# Screen_v3.net
KiCad netlist of a schematic drawn in EAGLE
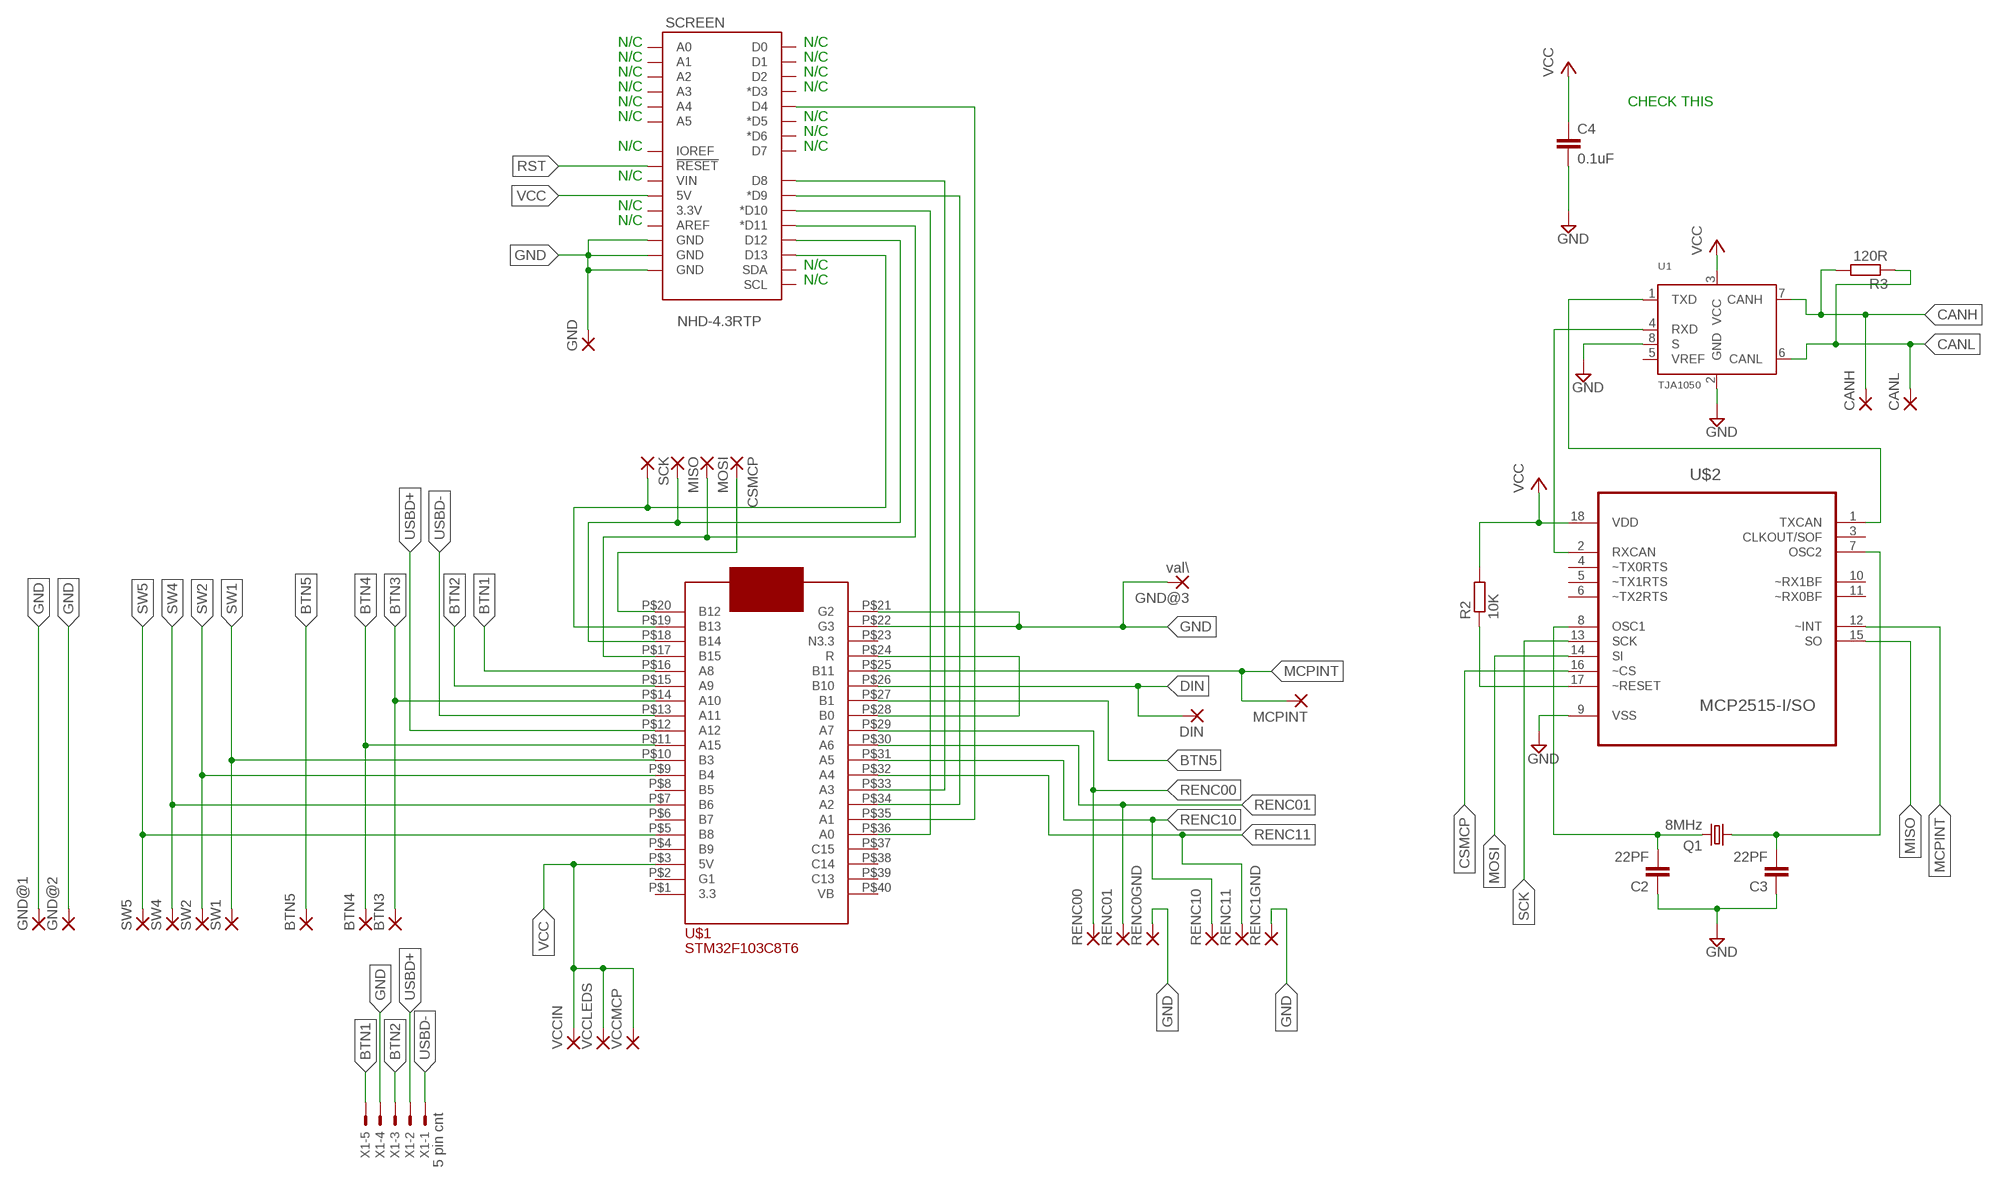
[diagram p0: schematic, sheet 1]

(export (version "E")
  (design (tool "Eeschema 10.0.6"))
  (components
    (comp (ref "BTN3")
      (value "SMD5")
      (footprint "eagle-import:SMD2,54-5,08")
      (libsource (lib "eagle-import") (part "SMD5"))
    )
    (comp (ref "BTN4")
      (value "SMD5")
      (footprint "eagle-import:SMD2,54-5,08")
      (libsource (lib "eagle-import") (part "SMD5"))
    )
    (comp (ref "BTN5")
      (value "SMD5")
      (footprint "eagle-import:SMD2,54-5,08")
      (libsource (lib "eagle-import") (part "SMD5"))
    )
    (comp (ref "C2")
      (value "22PF")
      (footprint "eagle-import:C0805")
      (libsource (lib "eagle-import") (part "C-EUC0805"))
    )
    (comp (ref "C3")
      (value "22PF")
      (footprint "eagle-import:C0805")
      (libsource (lib "eagle-import") (part "C-EUC0805"))
    )
    (comp (ref "C4")
      (value "0.1uF")
      (footprint "eagle-import:C0805")
      (libsource (lib "eagle-import") (part "C-EUC0805"))
    )
    (comp (ref "CANH")
      (value "SMD5")
      (footprint "eagle-import:SMD2,54-5,08")
      (libsource (lib "eagle-import") (part "SMD5"))
    )
    (comp (ref "CANL")
      (value "SMD5")
      (footprint "eagle-import:SMD2,54-5,08")
      (libsource (lib "eagle-import") (part "SMD5"))
    )
    (comp (ref "CSMCP")
      (value "SMD5")
      (footprint "eagle-import:SMD2,54-5,08")
      (libsource (lib "eagle-import") (part "SMD5"))
    )
    (comp (ref "DIN")
      (value "SMD5")
      (footprint "eagle-import:SMD2,54-5,08")
      (libsource (lib "eagle-import") (part "SMD5"))
    )
    (comp (ref "GND")
      (value "SMD5")
      (footprint "eagle-import:SMD2,54-5,08")
      (libsource (lib "eagle-import") (part "SMD5"))
    )
    (comp (ref "GND@1")
      (value "SMD5")
      (footprint "eagle-import:SMD2,54-5,08")
      (libsource (lib "eagle-import") (part "SMD5"))
    )
    (comp (ref "GND@2")
      (value "SMD5")
      (footprint "eagle-import:SMD2,54-5,08")
      (libsource (lib "eagle-import") (part "SMD5"))
    )
    (comp (ref "GND@3")
      (value "val\\")
      (footprint "eagle-import:SMD2,54-5,08")
      (libsource (lib "eagle-import") (part "SMD5"))
    )
    (comp (ref "MCPINT")
      (value "SMD5")
      (footprint "eagle-import:SMD2,54-5,08")
      (libsource (lib "eagle-import") (part "SMD5"))
    )
    (comp (ref "MISO")
      (value "SMD5")
      (footprint "eagle-import:SMD2,54-5,08")
      (libsource (lib "eagle-import") (part "SMD5"))
    )
    (comp (ref "MOSI")
      (value "SMD5")
      (footprint "eagle-import:SMD2,54-5,08")
      (libsource (lib "eagle-import") (part "SMD5"))
    )
    (comp (ref "Q1")
      (value "8MHz")
      (footprint "eagle-import:HC49_S")
      (libsource (lib "eagle-import") (part "CRYSTALHC49S"))
    )
    (comp (ref "R2")
      (value "10K")
      (footprint "eagle-import:M0805")
      (libsource (lib "eagle-import") (part "R-EU_M0805"))
    )
    (comp (ref "R3")
      (value "120R")
      (footprint "eagle-import:M0805")
      (libsource (lib "eagle-import") (part "R-EU_M0805"))
    )
    (comp (ref "RENC00")
      (value "SMD5")
      (footprint "eagle-import:SMD2,54-5,08")
      (libsource (lib "eagle-import") (part "SMD5"))
    )
    (comp (ref "RENC0GND")
      (value "SMD5")
      (footprint "eagle-import:SMD2,54-5,08")
      (libsource (lib "eagle-import") (part "SMD5"))
    )
    (comp (ref "RENC01")
      (value "SMD5")
      (footprint "eagle-import:SMD2,54-5,08")
      (libsource (lib "eagle-import") (part "SMD5"))
    )
    (comp (ref "RENC1GND")
      (value "SMD5")
      (footprint "eagle-import:SMD2,54-5,08")
      (libsource (lib "eagle-import") (part "SMD5"))
    )
    (comp (ref "RENC10")
      (value "SMD5")
      (footprint "eagle-import:SMD2,54-5,08")
      (libsource (lib "eagle-import") (part "SMD5"))
    )
    (comp (ref "RENC11")
      (value "SMD5")
      (footprint "eagle-import:SMD2,54-5,08")
      (libsource (lib "eagle-import") (part "SMD5"))
    )
    (comp (ref "SCK")
      (value "SMD5")
      (footprint "eagle-import:SMD2,54-5,08")
      (libsource (lib "eagle-import") (part "SMD5"))
    )
    (comp (ref "SCREEN")
      (value "NHD-4.3RTP")
      (footprint "eagle-import:NHD-4.3RTP")
      (libsource (lib "eagle-import") (part "NHD-4.3RTP"))
    )
    (comp (ref "SW1")
      (value "SMD5")
      (footprint "eagle-import:SMD2,54-5,08")
      (libsource (lib "eagle-import") (part "SMD5"))
    )
    (comp (ref "SW2")
      (value "SMD5")
      (footprint "eagle-import:SMD2,54-5,08")
      (libsource (lib "eagle-import") (part "SMD5"))
    )
    (comp (ref "SW4")
      (value "SMD5")
      (footprint "eagle-import:SMD2,54-5,08")
      (libsource (lib "eagle-import") (part "SMD5"))
    )
    (comp (ref "SW5")
      (value "SMD5")
      (footprint "eagle-import:SMD2,54-5,08")
      (libsource (lib "eagle-import") (part "SMD5"))
    )
    (comp (ref "U$1")
      (value "STM32F103C8T6DIP40")
      (footprint "eagle-import:STM32")
      (libsource (lib "eagle-import") (part "STM32F103C8T6DIP40"))
    )
    (comp (ref "U$2")
      (value "MCP2515-I/SO")
      (footprint "eagle-import:SOIC127P1034X264-18N")
      (fields (field (name "MF") "Microchip"))
      (libsource (lib "eagle-import") (part "MCP2515-I/SO"))
    )
    (comp (ref "U1")
      (value "TJA1050")
      (footprint "eagle-import:SOT96-1")
      (fields (field (name "MF") "NXP Semiconductors"))
      (libsource (lib "eagle-import") (part "TJA1050"))
    )
    (comp (ref "VCCIN")
      (value "SMD5")
      (footprint "eagle-import:SMD2,54-5,08")
      (libsource (lib "eagle-import") (part "SMD5"))
    )
    (comp (ref "VCCLEDS")
      (value "SMD5")
      (footprint "eagle-import:SMD2,54-5,08")
      (libsource (lib "eagle-import") (part "SMD5"))
    )
    (comp (ref "VCCMCP")
      (value "SMD5")
      (footprint "eagle-import:SMD2,54-5,08")
      (libsource (lib "eagle-import") (part "SMD5"))
    )
    (comp (ref "X1")
      (value "5 pin cnt")
      (footprint "eagle-import:JST-XH-05-PACKAGE-ROUND-PAD")
      (libsource (lib "eagle-import") (part "JST-XH-05-PIN-ROUND-PAD"))
    )
  )
  (nets
    (net (code "1") (name "BTN1") (class "Default")
      (node (ref "U$1") (pin "P$16") (pinfunction "A8_P$16") (pintype "bidirectional"))
      (node (ref "X1") (pin "5") (pinfunction "S_5") (pintype "passive"))
    )
    (net (code "2") (name "BTN2") (class "Default")
      (node (ref "U$1") (pin "P$15") (pinfunction "A9_P$15") (pintype "bidirectional"))
      (node (ref "X1") (pin "3") (pinfunction "S_3") (pintype "passive"))
    )
    (net (code "3") (name "BTN3") (class "Default")
      (node (ref "BTN3") (pin "1") (pinfunction "P_1") (pintype "passive"))
      (node (ref "U$1") (pin "P$14") (pinfunction "A10_P$14") (pintype "bidirectional"))
    )
    (net (code "4") (name "BTN4") (class "Default")
      (node (ref "BTN4") (pin "1") (pinfunction "P_1") (pintype "passive"))
      (node (ref "U$1") (pin "P$11") (pinfunction "A15_P$11") (pintype "bidirectional"))
    )
    (net (code "5") (name "BTN5") (class "Default")
      (node (ref "BTN5") (pin "1") (pinfunction "P_1") (pintype "passive"))
      (node (ref "U$1") (pin "P$27") (pinfunction "B1_P$27") (pintype "bidirectional"))
    )
    (net (code "6") (name "CANH") (class "Default")
      (node (ref "CANH") (pin "1") (pinfunction "P_1") (pintype "passive"))
      (node (ref "R3") (pin "2") (pinfunction "2_2") (pintype "passive"))
      (node (ref "U1") (pin "7") (pinfunction "CANH_7") (pintype "bidirectional"))
    )
    (net (code "7") (name "CANL") (class "Default")
      (node (ref "CANL") (pin "1") (pinfunction "P_1") (pintype "passive"))
      (node (ref "R3") (pin "1") (pinfunction "1_1") (pintype "passive"))
      (node (ref "U1") (pin "6") (pinfunction "CANL_6") (pintype "bidirectional"))
    )
    (net (code "8") (name "CSMCP") (class "Default")
      (node (ref "CSMCP") (pin "1") (pinfunction "P_1") (pintype "passive"))
      (node (ref "U$1") (pin "P$20") (pinfunction "B12_P$20") (pintype "bidirectional"))
      (node (ref "U$2") (pin "16") (pinfunction "~{CS}_16") (pintype "input"))
    )
    (net (code "9") (name "DIN") (class "Default")
      (node (ref "DIN") (pin "1") (pinfunction "P_1") (pintype "passive"))
      (node (ref "U$1") (pin "P$26") (pinfunction "B10_P$26") (pintype "bidirectional"))
    )
    (net (code "10") (name "GND") (class "Default")
      (node (ref "C2") (pin "1") (pinfunction "1_1") (pintype "passive"))
      (node (ref "C3") (pin "1") (pinfunction "1_1") (pintype "passive"))
      (node (ref "C4") (pin "2") (pinfunction "2_2") (pintype "passive"))
      (node (ref "GND") (pin "1") (pinfunction "P_1") (pintype "passive"))
      (node (ref "GND@1") (pin "1") (pinfunction "P_1") (pintype "passive"))
      (node (ref "GND@2") (pin "1") (pinfunction "P_1") (pintype "passive"))
      (node (ref "GND@3") (pin "1") (pinfunction "P_1") (pintype "passive"))
      (node (ref "RENC0GND") (pin "1") (pinfunction "P_1") (pintype "passive"))
      (node (ref "RENC1GND") (pin "1") (pinfunction "P_1") (pintype "passive"))
      (node (ref "SCREEN") (pin "GND@1") (pinfunction "GND_GND@1") (pintype "bidirectional"))
      (node (ref "SCREEN") (pin "GND@2") (pinfunction "GND_GND@2") (pintype "bidirectional"))
      (node (ref "SCREEN") (pin "GND@3") (pinfunction "GND_GND@3") (pintype "bidirectional"))
      (node (ref "U$1") (pin "P$21") (pinfunction "G2_P$21") (pintype "bidirectional"))
      (node (ref "U$1") (pin "P$22") (pinfunction "G3_P$22") (pintype "bidirectional"))
      (node (ref "U$2") (pin "9") (pinfunction "VSS_9") (pintype "power_in"))
      (node (ref "U1") (pin "2") (pinfunction "GND_2") (pintype "bidirectional"))
      (node (ref "U1") (pin "8") (pinfunction "S_8") (pintype "power_in"))
      (node (ref "X1") (pin "4") (pinfunction "S_4") (pintype "passive"))
    )
    (net (code "11") (name "MCPINT") (class "Default")
      (node (ref "MCPINT") (pin "1") (pinfunction "P_1") (pintype "passive"))
      (node (ref "U$1") (pin "P$25") (pinfunction "B11_P$25") (pintype "bidirectional"))
      (node (ref "U$2") (pin "12") (pinfunction "~{INT}_12") (pintype "output"))
    )
    (net (code "12") (name "MISO") (class "Default")
      (node (ref "MISO") (pin "1") (pinfunction "P_1") (pintype "passive"))
      (node (ref "SCREEN") (pin "D12") (pinfunction "D12_D12") (pintype "bidirectional"))
      (node (ref "U$1") (pin "P$18") (pinfunction "B14_P$18") (pintype "bidirectional"))
      (node (ref "U$2") (pin "15") (pinfunction "SO_15") (pintype "output"))
    )
    (net (code "13") (name "MOSI") (class "Default")
      (node (ref "MOSI") (pin "1") (pinfunction "P_1") (pintype "passive"))
      (node (ref "SCREEN") (pin "D11") (pinfunction "*D11_D11") (pintype "bidirectional"))
      (node (ref "U$1") (pin "P$17") (pinfunction "B15_P$17") (pintype "bidirectional"))
      (node (ref "U$2") (pin "14") (pinfunction "SI_14") (pintype "input"))
    )
    (net (code "14") (name "Net-(SCREEN-*D9)") (class "Default")
      (node (ref "SCREEN") (pin "D9") (pinfunction "*D9_D9") (pintype "bidirectional"))
      (node (ref "U$1") (pin "P$34") (pinfunction "A2_P$34") (pintype "bidirectional"))
    )
    (net (code "15") (name "Net-(SCREEN-*D10)") (class "Default")
      (node (ref "SCREEN") (pin "D10") (pinfunction "*D10_D10") (pintype "bidirectional"))
      (node (ref "U$1") (pin "P$36") (pinfunction "A0_P$36") (pintype "bidirectional"))
    )
    (net (code "16") (name "Net-(U$1-A1)") (class "Default")
      (node (ref "SCREEN") (pin "D4") (pinfunction "D4_D4") (pintype "bidirectional"))
      (node (ref "U$1") (pin "P$35") (pinfunction "A1_P$35") (pintype "bidirectional"))
    )
    (net (code "17") (name "Net-(U$1-A3)") (class "Default")
      (node (ref "SCREEN") (pin "D8") (pinfunction "D8_D8") (pintype "bidirectional"))
      (node (ref "U$1") (pin "P$33") (pinfunction "A3_P$33") (pintype "bidirectional"))
    )
    (net (code "18") (name "Net-(U$1-B0)") (class "Default")
      (node (ref "U$1") (pin "P$24") (pinfunction "R_P$24") (pintype "bidirectional"))
      (node (ref "U$1") (pin "P$28") (pinfunction "B0_P$28") (pintype "bidirectional"))
    )
    (net (code "19") (name "Net-(U$2-OSC1)") (class "Default")
      (node (ref "C2") (pin "2") (pinfunction "2_2") (pintype "passive"))
      (node (ref "Q1") (pin "2") (pinfunction "2_2") (pintype "passive"))
      (node (ref "U$2") (pin "8") (pinfunction "OSC1_8") (pintype "input"))
    )
    (net (code "20") (name "Net-(U$2-OSC2)") (class "Default")
      (node (ref "C3") (pin "2") (pinfunction "2_2") (pintype "passive"))
      (node (ref "Q1") (pin "1") (pinfunction "1_1") (pintype "passive"))
      (node (ref "U$2") (pin "7") (pinfunction "OSC2_7") (pintype "output"))
    )
    (net (code "21") (name "Net-(U$2-RXCAN)") (class "Default")
      (node (ref "U$2") (pin "2") (pinfunction "RXCAN_2") (pintype "input"))
      (node (ref "U1") (pin "4") (pinfunction "RXD_4") (pintype "bidirectional"))
    )
    (net (code "22") (name "Net-(U$2-TXCAN)") (class "Default")
      (node (ref "U$2") (pin "1") (pinfunction "TXCAN_1") (pintype "output"))
      (node (ref "U1") (pin "1") (pinfunction "TXD_1") (pintype "output"))
    )
    (net (code "23") (name "Net-(U$2-~{RESET})") (class "Default")
      (node (ref "R2") (pin "1") (pinfunction "1_1") (pintype "passive"))
      (node (ref "U$2") (pin "17") (pinfunction "~{RESET}_17") (pintype "input"))
    )
    (net (code "24") (name "RENC00") (class "Default")
      (node (ref "RENC00") (pin "1") (pinfunction "P_1") (pintype "passive"))
      (node (ref "U$1") (pin "P$29") (pinfunction "A7_P$29") (pintype "bidirectional"))
    )
    (net (code "25") (name "RENC01") (class "Default")
      (node (ref "RENC01") (pin "1") (pinfunction "P_1") (pintype "passive"))
      (node (ref "U$1") (pin "P$30") (pinfunction "A6_P$30") (pintype "bidirectional"))
    )
    (net (code "26") (name "RENC10") (class "Default")
      (node (ref "RENC10") (pin "1") (pinfunction "P_1") (pintype "passive"))
      (node (ref "U$1") (pin "P$31") (pinfunction "A5_P$31") (pintype "bidirectional"))
    )
    (net (code "27") (name "RENC11") (class "Default")
      (node (ref "RENC11") (pin "1") (pinfunction "P_1") (pintype "passive"))
      (node (ref "U$1") (pin "P$32") (pinfunction "A4_P$32") (pintype "bidirectional"))
    )
    (net (code "28") (name "RST") (class "Default")
      (node (ref "SCREEN") (pin "RESET@1") (pinfunction "~{RESET}_RESET@1") (pintype "bidirectional"))
    )
    (net (code "29") (name "SCK") (class "Default")
      (node (ref "SCK") (pin "1") (pinfunction "P_1") (pintype "passive"))
      (node (ref "SCREEN") (pin "D13") (pinfunction "D13_D13") (pintype "bidirectional"))
      (node (ref "U$1") (pin "P$19") (pinfunction "B13_P$19") (pintype "bidirectional"))
      (node (ref "U$2") (pin "13") (pinfunction "SCK_13") (pintype "input"))
    )
    (net (code "30") (name "SW1") (class "Default")
      (node (ref "SW1") (pin "1") (pinfunction "P_1") (pintype "passive"))
      (node (ref "U$1") (pin "P$10") (pinfunction "B3_P$10") (pintype "bidirectional"))
    )
    (net (code "31") (name "SW2") (class "Default")
      (node (ref "SW2") (pin "1") (pinfunction "P_1") (pintype "passive"))
      (node (ref "U$1") (pin "P$9") (pinfunction "B4_P$9") (pintype "bidirectional"))
    )
    (net (code "32") (name "SW4") (class "Default")
      (node (ref "SW4") (pin "1") (pinfunction "P_1") (pintype "passive"))
      (node (ref "U$1") (pin "P$7") (pinfunction "B6_P$7") (pintype "bidirectional"))
    )
    (net (code "33") (name "SW5") (class "Default")
      (node (ref "SW5") (pin "1") (pinfunction "P_1") (pintype "passive"))
      (node (ref "U$1") (pin "P$5") (pinfunction "B8_P$5") (pintype "bidirectional"))
    )
    (net (code "34") (name "USBD+") (class "Default")
      (node (ref "U$1") (pin "P$12") (pinfunction "A12_P$12") (pintype "bidirectional"))
      (node (ref "X1") (pin "2") (pinfunction "S_2") (pintype "passive"))
    )
    (net (code "35") (name "USBD-") (class "Default")
      (node (ref "U$1") (pin "P$13") (pinfunction "A11_P$13") (pintype "bidirectional"))
      (node (ref "X1") (pin "1") (pinfunction "S_1") (pintype "passive"))
    )
    (net (code "36") (name "VCC") (class "Default")
      (node (ref "C4") (pin "1") (pinfunction "1_1") (pintype "passive"))
      (node (ref "R2") (pin "2") (pinfunction "2_2") (pintype "passive"))
      (node (ref "SCREEN") (pin "5V") (pinfunction "5V_5V") (pintype "bidirectional"))
      (node (ref "U$1") (pin "P$3") (pinfunction "5V_P$3") (pintype "bidirectional"))
      (node (ref "U$2") (pin "18") (pinfunction "VDD_18") (pintype "power_in"))
      (node (ref "U1") (pin "3") (pinfunction "VCC_3") (pintype "bidirectional"))
      (node (ref "VCCIN") (pin "1") (pinfunction "P_1") (pintype "passive"))
      (node (ref "VCCLEDS") (pin "1") (pinfunction "P_1") (pintype "passive"))
      (node (ref "VCCMCP") (pin "1") (pinfunction "P_1") (pintype "passive"))
    )
    (net (code "37") (name "unconnected-(SCREEN-*D3-PadD3)") (class "Default")
      (node (ref "SCREEN") (pin "D3") (pinfunction "*D3_D3") (pintype "bidirectional"))
    )
    (net (code "38") (name "unconnected-(SCREEN-*D5-PadD5)") (class "Default")
      (node (ref "SCREEN") (pin "D5") (pinfunction "*D5_D5") (pintype "bidirectional"))
    )
    (net (code "39") (name "unconnected-(SCREEN-*D6-PadD6)") (class "Default")
      (node (ref "SCREEN") (pin "D6") (pinfunction "*D6_D6") (pintype "bidirectional"))
    )
    (net (code "40") (name "unconnected-(SCREEN-Pad3.3V)") (class "Default")
      (node (ref "SCREEN") (pin "3.3V") (pinfunction "3.3V_3.3V") (pintype "bidirectional"))
    )
    (net (code "41") (name "unconnected-(SCREEN-PadA0)") (class "Default")
      (node (ref "SCREEN") (pin "A0") (pinfunction "A0_A0") (pintype "bidirectional"))
    )
    (net (code "42") (name "unconnected-(SCREEN-PadA1)") (class "Default")
      (node (ref "SCREEN") (pin "A1") (pinfunction "A1_A1") (pintype "bidirectional"))
    )
    (net (code "43") (name "unconnected-(SCREEN-PadA2)") (class "Default")
      (node (ref "SCREEN") (pin "A2") (pinfunction "A2_A2") (pintype "bidirectional"))
    )
    (net (code "44") (name "unconnected-(SCREEN-PadA3)") (class "Default")
      (node (ref "SCREEN") (pin "A3") (pinfunction "A3_A3") (pintype "bidirectional"))
    )
    (net (code "45") (name "unconnected-(SCREEN-PadA4)") (class "Default")
      (node (ref "SCREEN") (pin "A4") (pinfunction "A4_A4") (pintype "bidirectional"))
    )
    (net (code "46") (name "unconnected-(SCREEN-PadA5)") (class "Default")
      (node (ref "SCREEN") (pin "A5") (pinfunction "A5_A5") (pintype "bidirectional"))
    )
    (net (code "47") (name "unconnected-(SCREEN-PadAREF)") (class "Default")
      (node (ref "SCREEN") (pin "AREF") (pinfunction "AREF_AREF") (pintype "bidirectional"))
    )
    (net (code "48") (name "unconnected-(SCREEN-PadD0)") (class "Default")
      (node (ref "SCREEN") (pin "D0") (pinfunction "D0_D0") (pintype "bidirectional"))
    )
    (net (code "49") (name "unconnected-(SCREEN-PadD1)") (class "Default")
      (node (ref "SCREEN") (pin "D1") (pinfunction "D1_D1") (pintype "bidirectional"))
    )
    (net (code "50") (name "unconnected-(SCREEN-PadD2)") (class "Default")
      (node (ref "SCREEN") (pin "D2") (pinfunction "D2_D2") (pintype "bidirectional"))
    )
    (net (code "51") (name "unconnected-(SCREEN-PadD7)") (class "Default")
      (node (ref "SCREEN") (pin "D7") (pinfunction "D7_D7") (pintype "bidirectional"))
    )
    (net (code "52") (name "unconnected-(SCREEN-PadIOREF)") (class "Default")
      (node (ref "SCREEN") (pin "IOREF") (pinfunction "IOREF_IOREF") (pintype "bidirectional"))
    )
    (net (code "53") (name "unconnected-(SCREEN-PadSCL)") (class "Default")
      (node (ref "SCREEN") (pin "SCL") (pinfunction "SCL_SCL") (pintype "bidirectional"))
    )
    (net (code "54") (name "unconnected-(SCREEN-PadSDA)") (class "Default")
      (node (ref "SCREEN") (pin "SDA") (pinfunction "SDA_SDA") (pintype "bidirectional"))
    )
    (net (code "55") (name "unconnected-(SCREEN-PadVIN)") (class "Default")
      (node (ref "SCREEN") (pin "VIN") (pinfunction "VIN_VIN") (pintype "bidirectional"))
    )
    (net (code "56") (name "unconnected-(U$1-3.3-PadP$1)") (class "Default")
      (node (ref "U$1") (pin "P$1") (pinfunction "3.3_P$1") (pintype "bidirectional"))
    )
    (net (code "57") (name "unconnected-(U$1-B5-PadP$8)") (class "Default")
      (node (ref "U$1") (pin "P$8") (pinfunction "B5_P$8") (pintype "bidirectional"))
    )
    (net (code "58") (name "unconnected-(U$1-B7-PadP$6)") (class "Default")
      (node (ref "U$1") (pin "P$6") (pinfunction "B7_P$6") (pintype "bidirectional"))
    )
    (net (code "59") (name "unconnected-(U$1-B9-PadP$4)") (class "Default")
      (node (ref "U$1") (pin "P$4") (pinfunction "B9_P$4") (pintype "bidirectional"))
    )
    (net (code "60") (name "unconnected-(U$1-C13-PadP$39)") (class "Default")
      (node (ref "U$1") (pin "P$39") (pinfunction "C13_P$39") (pintype "bidirectional"))
    )
    (net (code "61") (name "unconnected-(U$1-C14-PadP$38)") (class "Default")
      (node (ref "U$1") (pin "P$38") (pinfunction "C14_P$38") (pintype "bidirectional"))
    )
    (net (code "62") (name "unconnected-(U$1-C15-PadP$37)") (class "Default")
      (node (ref "U$1") (pin "P$37") (pinfunction "C15_P$37") (pintype "bidirectional"))
    )
    (net (code "63") (name "unconnected-(U$1-G1-PadP$2)") (class "Default")
      (node (ref "U$1") (pin "P$2") (pinfunction "G1_P$2") (pintype "bidirectional"))
    )
    (net (code "64") (name "unconnected-(U$1-N3.3-PadP$23)") (class "Default")
      (node (ref "U$1") (pin "P$23") (pinfunction "N3.3_P$23") (pintype "bidirectional"))
    )
    (net (code "65") (name "unconnected-(U$1-VB-PadP$40)") (class "Default")
      (node (ref "U$1") (pin "P$40") (pinfunction "VB_P$40") (pintype "bidirectional"))
    )
    (net (code "66") (name "unconnected-(U$2-CLKOUT{slash}SOF-Pad3)") (class "Default")
      (node (ref "U$2") (pin "3") (pinfunction "CLKOUT/SOF_3") (pintype "output"))
    )
    (net (code "67") (name "unconnected-(U$2-~{RX0BF}-Pad11)") (class "Default")
      (node (ref "U$2") (pin "11") (pinfunction "~{RX0BF}_11") (pintype "output"))
    )
    (net (code "68") (name "unconnected-(U$2-~{RX1BF}-Pad10)") (class "Default")
      (node (ref "U$2") (pin "10") (pinfunction "~{RX1BF}_10") (pintype "output"))
    )
    (net (code "69") (name "unconnected-(U$2-~{TX0RTS}-Pad4)") (class "Default")
      (node (ref "U$2") (pin "4") (pinfunction "~{TX0RTS}_4") (pintype "input"))
    )
    (net (code "70") (name "unconnected-(U$2-~{TX1RTS}-Pad5)") (class "Default")
      (node (ref "U$2") (pin "5") (pinfunction "~{TX1RTS}_5") (pintype "input"))
    )
    (net (code "71") (name "unconnected-(U$2-~{TX2RTS}-Pad6)") (class "Default")
      (node (ref "U$2") (pin "6") (pinfunction "~{TX2RTS}_6") (pintype "input"))
    )
    (net (code "72") (name "unconnected-(U1-VREF-Pad5)") (class "Default")
      (node (ref "U1") (pin "5") (pinfunction "VREF_5") (pintype "passive"))
    )
  )
)
